# CAN_24bit_airspeed.net
KiCad netlist of a schematic drawn in Altium Designer
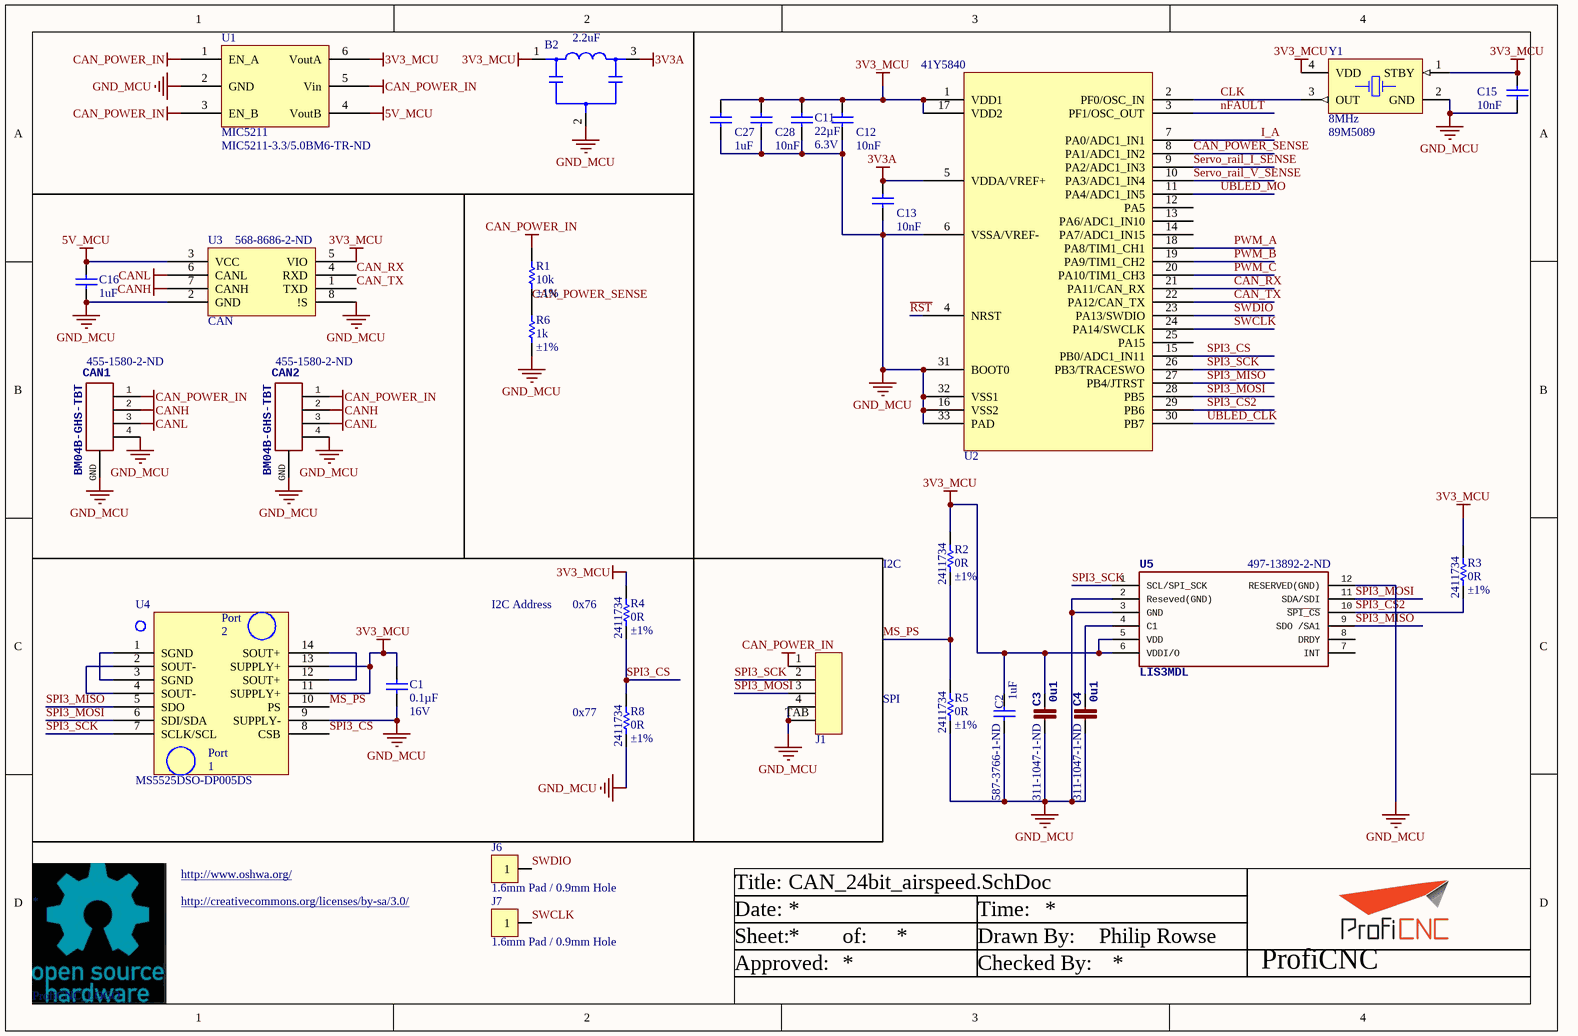
[diagram p0: CAN_24bit_airspeed.SchDoc]

(export (version "E")
  (design (tool "Eeschema 10.0.6"))
  (components
    (comp (ref "*")
      (value "ProfiCNC_LOGO")
      (footprint "ProfiCNC_medium")
      (libsource (lib "ProfiCNC") (part "ProfiCNC_LOGO"))
    )
    (comp (ref "B2")
      (value "2.2uF")
      (footprint "NFM18CC")
      (description "EMIFIL (Capacitor type) Single Circuit Type for Signal Lines")
      (fields
        (field (name "PARTNUMBER") "NFM18PC225B1A3D")
        (field (name "MANUFACTURER") "Murata Electronics North America")
      )
      (libsource (lib "Thiemar Shared Components") (part "NFM18CC222R1C3"))
    )
    (comp (ref "C1")
      (value "0.1µF")
      (footprint "C0402")
      (description "CAP CER 0.1UF 16V X7R 0402")
      (fields
        (field (name "VOLTAGE") "16V")
        (field (name "PART NUMBER") "C01050")
        (field (name "MANUFACTURER") "Murata Electronics North America")
      )
      (libsource (lib "open-components") (part "CAP"))
    )
    (comp (ref "C2")
      (value "1uF")
      (footprint "CAPC1005L")
      (description "CAP CER 1UF 6.3V X5R 0402")
      (fields
        (field (name "PARTNUMBER") "JMK105BJ105KVHF")
        (field (name "SUPPLIER PART NUMBER 1") "587-3766-1-ND")
        (field (name "Comment") "Cap")
      )
      (libsource (lib "Miscellaneous Devices") (part "Cap"))
    )
    (comp (ref "C3")
      (value "0u1")
      (footprint "C0402")
      (description "CAP CER 0.1UF 16V Y5V 0402")
      (fields
        (field (name "SUPPLIER PART NUMBER 1") "311-1047-1-ND")
        (field (name "3DR_PARTNO") "ECM0700")
        (field (name "PARTNO") "CC0402ZRY5V7BB104")
      )
      (libsource (lib "pixhawk2") (part "CAP0402"))
    )
    (comp (ref "C4")
      (value "0u1")
      (footprint "C0402")
      (description "CAP CER 0.1UF 16V Y5V 0402")
      (fields
        (field (name "SUPPLIER PART NUMBER 1") "311-1047-1-ND")
        (field (name "3DR_PARTNO") "ECM0700")
        (field (name "PARTNO") "CC0402ZRY5V7BB104")
      )
      (libsource (lib "pixhawk2") (part "CAP0402"))
    )
    (comp (ref "C11")
      (value "22µF")
      (footprint "C0805")
      (description "CAP CER 22UF 6.3V X5R 0805")
      (fields
        (field (name "VOLTAGE") "6.3V")
        (field (name "PART NUMBER") "C01690")
        (field (name "MANUFACTURER") "Murata Electronics North America")
      )
      (libsource (lib "open-components") (part "CAP"))
    )
    (comp (ref "C12")
      (value "10nF")
      (footprint "CAPC1005L")
      (description "CAP CER 10000PF 50V X7R 0402")
      (fields (field (name "PARTNUMBER") "CGA2B3X7R1H103K050BB"))
      (libsource (lib "Miscellaneous Devices") (part "Cap"))
    )
    (comp (ref "C13")
      (value "10nF")
      (footprint "CAPC1005L")
      (description "CAP CER 10000PF 50V X7R 0402")
      (fields (field (name "PARTNUMBER") "CGA2B3X7R1H103K050BB"))
      (libsource (lib "Miscellaneous Devices") (part "Cap"))
    )
    (comp (ref "C15")
      (value "10nF")
      (footprint "CAPC1005L")
      (description "CAP CER 10000PF 50V X7R 0402")
      (fields (field (name "PARTNUMBER") "CGA2B3X7R1H103K050BB"))
      (libsource (lib "Miscellaneous Devices") (part "Cap"))
    )
    (comp (ref "C16")
      (value "1uF")
      (footprint "CAPC1005L")
      (description "CAP CER 1UF 6.3V X5R 0402")
      (fields (field (name "PARTNUMBER") "JMK105BJ105KVHF") (field (name "Comment") "Cap"))
      (libsource (lib "Miscellaneous Devices") (part "Cap"))
    )
    (comp (ref "C27")
      (value "1uF")
      (footprint "CAPC1005L")
      (description "CAP CER 1UF 6.3V X5R 0402")
      (fields (field (name "PARTNUMBER") "JMK105BJ105KVHF") (field (name "Comment") "Cap"))
      (libsource (lib "Miscellaneous Devices") (part "Cap"))
    )
    (comp (ref "C28")
      (value "10nF")
      (footprint "CAPC1005L")
      (description "CAP CER 10000PF 50V X7R 0402")
      (fields (field (name "PARTNUMBER") "CGA2B3X7R1H103K050BB"))
      (libsource (lib "Miscellaneous Devices") (part "Cap"))
    )
    (comp (ref "CAN1")
      (value "BM04B-GHS-TBT")
      (footprint "BM04-GHS-TBT")
      (fields (field (name "PARTNO") "5023820470") (field (name "SUPPLIER PART NUMBER 1") "455-1580-2-ND"))
      (libsource (lib "ProfiCNC") (part "BM04B-GHS-TBT"))
    )
    (comp (ref "CAN2")
      (value "BM04B-GHS-TBT")
      (footprint "BM04-GHS-TBT")
      (fields (field (name "PARTNO") "5023820470") (field (name "SUPPLIER PART NUMBER 1") "455-1580-2-ND"))
      (libsource (lib "ProfiCNC") (part "BM04B-GHS-TBT"))
    )
    (comp (ref "J1")
      (value "HDR_TAB_1x4")
      (footprint "DF13C-4P-1.25V")
      (description "CONN HEADER 4POS 1.25MM SMD GOLD")
      (fields (field (name "PART NUMBER") "J00015") (field (name "MANUFACTURER") "Hirose Electric Co Ltd"))
      (libsource (lib "open-components") (part "HDR_TAB_1x4"))
    )
    (comp (ref "J6")
      (value "1.6mm Pad / 0.9mm Hole")
      (footprint "1.6mm Pad / 0.9mm Hole")
      (libsource (lib "ProfiCNC") (part "Connector 1x01"))
    )
    (comp (ref "J7")
      (value "1.6mm Pad / 0.9mm Hole")
      (footprint "1.6mm Pad / 0.9mm Hole")
      (libsource (lib "ProfiCNC") (part "Connector 1x01"))
    )
    (comp (ref "R1")
      (value "10k")
      (footprint "R0402")
      (description "RES SMD 10K OHM 1% 1/16W 0402")
      (fields
        (field (name "TOLERANCE") "±1%")
        (field (name "PART NUMBER") "R00142")
        (field (name "MANUFACTURER") "Yageo")
      )
      (libsource (lib "open-components") (part "RES"))
    )
    (comp (ref "R2")
      (value "0R")
      (footprint "R0402")
      (description "RES SMD 0R 1% 1/16W 0402")
      (fields
        (field (name "TOLERANCE") "±1%")
        (field (name "PART NUMBER") "R00094")
        (field (name "MANUFACTURER") "Yageo")
        (field (name "SUPPLIER PART NUMBER 1") "2411734")
      )
      (libsource (lib "open-components") (part "RES"))
    )
    (comp (ref "R3")
      (value "0R")
      (footprint "R0402")
      (description "RES SMD 0R 1% 1/16W 0402")
      (fields
        (field (name "TOLERANCE") "±1%")
        (field (name "PART NUMBER") "R00094")
        (field (name "MANUFACTURER") "Yageo")
        (field (name "SUPPLIER PART NUMBER 1") "2411734")
      )
      (libsource (lib "open-components") (part "RES"))
    )
    (comp (ref "R4")
      (value "0R")
      (footprint "R0402")
      (description "RES SMD 0R 1% 1/16W 0402")
      (fields
        (field (name "TOLERANCE") "±1%")
        (field (name "PART NUMBER") "R00094")
        (field (name "MANUFACTURER") "Yageo")
        (field (name "SUPPLIER PART NUMBER 1") "2411734")
      )
      (libsource (lib "open-components") (part "RES"))
    )
    (comp (ref "R5")
      (value "0R")
      (footprint "R0402")
      (description "RES SMD 0R 1% 1/16W 0402")
      (fields
        (field (name "TOLERANCE") "±1%")
        (field (name "PART NUMBER") "R00094")
        (field (name "MANUFACTURER") "Yageo")
        (field (name "SUPPLIER PART NUMBER 1") "2411734")
      )
      (libsource (lib "open-components") (part "RES"))
    )
    (comp (ref "R6")
      (value "1k")
      (footprint "R0402")
      (description "RES SMD 1K OHM 1% 1/16W 0402")
      (fields
        (field (name "TOLERANCE") "±1%")
        (field (name "PART NUMBER") "R00094")
        (field (name "MANUFACTURER") "Yageo")
      )
      (libsource (lib "open-components") (part "RES"))
    )
    (comp (ref "R8")
      (value "0R")
      (footprint "R0402")
      (description "RES SMD 0R 1% 1/16W 0402")
      (fields
        (field (name "TOLERANCE") "±1%")
        (field (name "PART NUMBER") "R00094")
        (field (name "MANUFACTURER") "Yageo")
        (field (name "SUPPLIER PART NUMBER 1") "2411734")
      )
      (libsource (lib "open-components") (part "RES"))
    )
    (comp (ref "U1")
      (value "MIC5211")
      (footprint "SOT23-6")
      (fields (field (name "SUPPLIER PART NUMBER 1") "MIC5211-3.3/5.0BM6-TR-ND"))
      (libsource (lib "ProfiCNC") (part "MIC5211"))
    )
    (comp (ref "U2")
      (value "IC MCU M4 64KB FLASH 32UFQFPN")
      (footprint "QFN50P500X500X60-32L")
      (description "72 MHz Cortex-M4F MCU with 16 KB RAM, 64 KB flash")
      (fields (field (name "PARTNUMBER") "STM32F302K8U6") (field (name "SUPPLIER PART NUMBER 1") "41Y5840"))
      (libsource (lib "Thiemar Shared Components") (part "STM32F302K8U6"))
    )
    (comp (ref "U3")
      (value "CAN")
      (footprint "SON65P300X100_HS-9N")
      (fields (field (name "SUPPLIER PART NUMBER 1") "568-8686-2-ND"))
      (libsource (lib "ProfiCNC") (part "CAN"))
    )
    (comp (ref "U4")
      (value "MS5525DSO-DP005DS")
      (footprint "MS5525DSO")
      (libsource (lib "ProfiCNC") (part "MS5525DSO-DP"))
    )
    (comp (ref "U5")
      (value "LIS3MDL")
      (footprint "LIS3MDL")
      (fields (field (name "PARTNO") "HMC5983") (field (name "SUPPLIER PART NUMBER 1") "497-13892-2-ND"))
      (libsource (lib "ProfiCNC") (part "LIS3MDL"))
    )
    (comp (ref "Y1")
      (value "8MHz")
      (footprint "CS325")
      (description "3.3V 8MHz XO Oscillator")
      (fields
        (field (name "PARTNUMBER") "ASE-8.000MHZ-LC-T")
        (field (name "MANUFACTURER") "Abracon Corporation")
        (field (name "SUPPLIER PART NUMBER 1") "89M5089")
      )
      (libsource (lib "Thiemar Shared Components") (part "ASE-12.000MHZ"))
    )
  )
  (nets
    (net (code "1") (name "/CAN_POWER_SENSE") (class "Default")
      (node (ref "R1") (pin "2") (pinfunction "2_2") (pintype "passive"))
      (node (ref "R6") (pin "1") (pinfunction "1_1") (pintype "passive"))
      (node (ref "U2") (pin "8") (pinfunction "PA1/ADC1_IN2_8") (pintype "passive"))
    )
    (net (code "2") (name "/CAN_RX") (class "Default")
      (node (ref "U2") (pin "21") (pinfunction "PA11/CAN_RX_21") (pintype "passive"))
      (node (ref "U3") (pin "4") (pinfunction "RXD_4") (pintype "passive"))
    )
    (net (code "3") (name "/CAN_TX") (class "Default")
      (node (ref "U2") (pin "22") (pinfunction "PA12/CAN_TX_22") (pintype "passive"))
      (node (ref "U3") (pin "1") (pinfunction "TXD_1") (pintype "passive"))
    )
    (net (code "4") (name "/CLK") (class "Default")
      (node (ref "U2") (pin "2") (pinfunction "PF0/OSC_IN_2") (pintype "passive"))
      (node (ref "Y1") (pin "3") (pinfunction "OUT_3") (pintype "output"))
    )
    (net (code "5") (name "/I_A") (class "Default")
      (node (ref "U2") (pin "7") (pinfunction "PA0/ADC1_IN1_7") (pintype "passive"))
    )
    (net (code "6") (name "/MS_PS") (class "Default")
      (node (ref "R2") (pin "2") (pinfunction "2_2") (pintype "passive"))
      (node (ref "R5") (pin "1") (pinfunction "1_1") (pintype "passive"))
      (node (ref "U4") (pin "10") (pinfunction "PS_10") (pintype "passive"))
    )
    (net (code "7") (name "/PWM_A") (class "Default")
      (node (ref "U2") (pin "18") (pinfunction "PA8/TIM1_CH1_18") (pintype "passive"))
    )
    (net (code "8") (name "/PWM_B") (class "Default")
      (node (ref "U2") (pin "19") (pinfunction "PA9/TIM1_CH2_19") (pintype "passive"))
    )
    (net (code "9") (name "/PWM_C") (class "Default")
      (node (ref "U2") (pin "20") (pinfunction "PA10/TIM1_CH3_20") (pintype "passive"))
    )
    (net (code "10") (name "/SPI3_CS") (class "Default")
      (node (ref "R4") (pin "2") (pinfunction "2_2") (pintype "passive"))
      (node (ref "R8") (pin "1") (pinfunction "1_1") (pintype "passive"))
      (node (ref "U2") (pin "15") (pinfunction "PB0/ADC1_IN11_15") (pintype "passive"))
      (node (ref "U4") (pin "8") (pinfunction "CSB_8") (pintype "passive"))
    )
    (net (code "11") (name "/SPI3_CS2") (class "Default")
      (node (ref "R3") (pin "2") (pinfunction "2_2") (pintype "passive"))
      (node (ref "U2") (pin "29") (pinfunction "PB6_29") (pintype "passive"))
      (node (ref "U5") (pin "10") (pinfunction "~{SPI_CS}_10") (pintype "passive"))
    )
    (net (code "12") (name "/SPI3_MISO") (class "Default")
      (node (ref "U2") (pin "27") (pinfunction "PB4/JTRST_27") (pintype "passive"))
      (node (ref "U4") (pin "5") (pinfunction "SDO_5") (pintype "passive"))
      (node (ref "U5") (pin "9") (pinfunction "SDO_/SA1_9") (pintype "passive"))
    )
    (net (code "13") (name "/SPI3_MOSI") (class "Default")
      (node (ref "J1") (pin "3") (pinfunction "3_3") (pintype "passive"))
      (node (ref "U2") (pin "28") (pinfunction "PB5_28") (pintype "passive"))
      (node (ref "U4") (pin "6") (pinfunction "SDI/SDA_6") (pintype "passive"))
      (node (ref "U5") (pin "11") (pinfunction "SDA/SDI_11") (pintype "passive"))
    )
    (net (code "14") (name "/SPI3_SCK") (class "Default")
      (node (ref "J1") (pin "2") (pinfunction "2_2") (pintype "passive"))
      (node (ref "U2") (pin "26") (pinfunction "PB3/TRACESWO_26") (pintype "passive"))
      (node (ref "U4") (pin "7") (pinfunction "SCLK/SCL_7") (pintype "passive"))
      (node (ref "U5") (pin "1") (pinfunction "SCL/SPI_SCK_1") (pintype "passive"))
    )
    (net (code "15") (name "/SWCLK") (class "Default")
      (node (ref "J7") (pin "1") (pinfunction "1_1") (pintype "passive"))
      (node (ref "U2") (pin "24") (pinfunction "PA14/SWCLK_24") (pintype "passive"))
    )
    (net (code "16") (name "/SWDIO") (class "Default")
      (node (ref "J6") (pin "1") (pinfunction "1_1") (pintype "passive"))
      (node (ref "U2") (pin "23") (pinfunction "PA13/SWDIO_23") (pintype "passive"))
    )
    (net (code "17") (name "/Servo_rail_I_SENSE") (class "Default")
      (node (ref "U2") (pin "9") (pinfunction "PA2/ADC1_IN3_9") (pintype "passive"))
    )
    (net (code "18") (name "/Servo_rail_V_SENSE") (class "Default")
      (node (ref "U2") (pin "10") (pinfunction "PA3/ADC1_IN4_10") (pintype "passive"))
    )
    (net (code "19") (name "/UBLED_CLK") (class "Default")
      (node (ref "U2") (pin "30") (pinfunction "PB7_30") (pintype "passive"))
    )
    (net (code "20") (name "/UBLED_MO") (class "Default")
      (node (ref "U2") (pin "11") (pinfunction "PA4/ADC1_IN5_11") (pintype "passive"))
    )
    (net (code "21") (name "/nFAULT") (class "Default")
      (node (ref "U2") (pin "3") (pinfunction "PF1/OSC_OUT_3") (pintype "passive"))
    )
    (net (code "22") (name "/~{RST}") (class "Default")
      (node (ref "U2") (pin "4") (pinfunction "NRST_4") (pintype "passive"))
    )
    (net (code "23") (name "3V3A") (class "Default")
      (node (ref "B2") (pin "3") (pinfunction "OUT_3") (pintype "passive"))
      (node (ref "C13") (pin "2") (pinfunction "2_2") (pintype "passive"))
      (node (ref "U2") (pin "5") (pinfunction "VDDA/VREF+_5") (pintype "passive"))
    )
    (net (code "24") (name "3V3_MCU") (class "Default")
      (node (ref "B2") (pin "1") (pinfunction "IN_1") (pintype "passive"))
      (node (ref "C1") (pin "1") (pinfunction "1_1") (pintype "passive"))
      (node (ref "C11") (pin "1") (pinfunction "1_1") (pintype "passive"))
      (node (ref "C12") (pin "2") (pinfunction "2_2") (pintype "passive"))
      (node (ref "C15") (pin "2") (pinfunction "2_2") (pintype "passive"))
      (node (ref "C2") (pin "1") (pinfunction "1_1") (pintype "passive"))
      (node (ref "C27") (pin "1") (pinfunction "1_1") (pintype "passive"))
      (node (ref "C28") (pin "2") (pinfunction "2_2") (pintype "passive"))
      (node (ref "C3") (pin "P$1") (pinfunction "1_P$1") (pintype "passive"))
      (node (ref "R2") (pin "1") (pinfunction "1_1") (pintype "passive"))
      (node (ref "R3") (pin "1") (pinfunction "1_1") (pintype "passive"))
      (node (ref "R4") (pin "1") (pinfunction "1_1") (pintype "passive"))
      (node (ref "U1") (pin "6") (pinfunction "VoutA_6") (pintype "passive"))
      (node (ref "U2") (pin "1") (pinfunction "VDD1_1") (pintype "passive"))
      (node (ref "U2") (pin "17") (pinfunction "VDD2_17") (pintype "passive"))
      (node (ref "U3") (pin "5") (pinfunction "VIO_5") (pintype "passive"))
      (node (ref "U4") (pin "11") (pinfunction "SUPPLY+_11") (pintype "passive"))
      (node (ref "U4") (pin "13") (pinfunction "SUPPLY+_13") (pintype "passive"))
      (node (ref "U5") (pin "5") (pinfunction "VDD_5") (pintype "passive"))
      (node (ref "U5") (pin "6") (pinfunction "VDDI/O_6") (pintype "passive"))
      (node (ref "Y1") (pin "1") (pinfunction "STBY_1") (pintype "input"))
      (node (ref "Y1") (pin "4") (pinfunction "VDD_4") (pintype "power_in"))
    )
    (net (code "25") (name "5V_MCU") (class "Default")
      (node (ref "C16") (pin "2") (pinfunction "2_2") (pintype "passive"))
      (node (ref "U1") (pin "4") (pinfunction "VoutB_4") (pintype "passive"))
      (node (ref "U3") (pin "3") (pinfunction "VCC_3") (pintype "passive"))
    )
    (net (code "26") (name "CANH") (class "Default")
      (node (ref "CAN1") (pin "2") (pinfunction "2_2") (pintype "passive"))
      (node (ref "CAN2") (pin "2") (pinfunction "2_2") (pintype "passive"))
      (node (ref "U3") (pin "7") (pinfunction "CANH_7") (pintype "passive"))
    )
    (net (code "27") (name "CANL") (class "Default")
      (node (ref "CAN1") (pin "3") (pinfunction "3_3") (pintype "passive"))
      (node (ref "CAN2") (pin "3") (pinfunction "3_3") (pintype "passive"))
      (node (ref "U3") (pin "6") (pinfunction "CANL_6") (pintype "passive"))
    )
    (net (code "28") (name "CAN_POWER_IN") (class "Default")
      (node (ref "CAN1") (pin "1") (pinfunction "1_1") (pintype "passive"))
      (node (ref "CAN2") (pin "1") (pinfunction "1_1") (pintype "passive"))
      (node (ref "J1") (pin "1") (pinfunction "1_1") (pintype "passive"))
      (node (ref "R1") (pin "1") (pinfunction "1_1") (pintype "passive"))
      (node (ref "U1") (pin "1") (pinfunction "EN_A_1") (pintype "power_in"))
      (node (ref "U1") (pin "3") (pinfunction "EN_B_3") (pintype "passive"))
      (node (ref "U1") (pin "5") (pinfunction "Vin_5") (pintype "passive"))
    )
    (net (code "29") (name "GND_MCU") (class "Default")
      (node (ref "B2") (pin "2") (pinfunction "GND_2") (pintype "passive"))
      (node (ref "C1") (pin "2") (pinfunction "2_2") (pintype "passive"))
      (node (ref "C11") (pin "2") (pinfunction "2_2") (pintype "passive"))
      (node (ref "C12") (pin "1") (pinfunction "1_1") (pintype "passive"))
      (node (ref "C13") (pin "1") (pinfunction "1_1") (pintype "passive"))
      (node (ref "C15") (pin "1") (pinfunction "1_1") (pintype "passive"))
      (node (ref "C16") (pin "1") (pinfunction "1_1") (pintype "passive"))
      (node (ref "C2") (pin "2") (pinfunction "2_2") (pintype "passive"))
      (node (ref "C27") (pin "2") (pinfunction "2_2") (pintype "passive"))
      (node (ref "C28") (pin "1") (pinfunction "1_1") (pintype "passive"))
      (node (ref "C3") (pin "P$2") (pinfunction "2_P$2") (pintype "passive"))
      (node (ref "C4") (pin "P$2") (pinfunction "2_P$2") (pintype "passive"))
      (node (ref "CAN1") (pin "4") (pinfunction "4_4") (pintype "passive"))
      (node (ref "CAN1") (pin "GND") (pinfunction "GND_GND") (pintype "passive"))
      (node (ref "CAN2") (pin "4") (pinfunction "4_4") (pintype "passive"))
      (node (ref "CAN2") (pin "GND") (pinfunction "GND_GND") (pintype "passive"))
      (node (ref "J1") (pin "4") (pinfunction "4_4") (pintype "passive"))
      (node (ref "J1") (pin "TAB") (pinfunction "TAB_TAB") (pintype "passive"))
      (node (ref "R5") (pin "2") (pinfunction "2_2") (pintype "passive"))
      (node (ref "R6") (pin "2") (pinfunction "2_2") (pintype "passive"))
      (node (ref "R8") (pin "2") (pinfunction "2_2") (pintype "passive"))
      (node (ref "U1") (pin "2") (pinfunction "GND_2") (pintype "power_in"))
      (node (ref "U2") (pin "16") (pinfunction "VSS2_16") (pintype "passive"))
      (node (ref "U2") (pin "31") (pinfunction "BOOT0_31") (pintype "passive"))
      (node (ref "U2") (pin "32") (pinfunction "VSS1_32") (pintype "passive"))
      (node (ref "U2") (pin "33") (pinfunction "PAD_33") (pintype "passive"))
      (node (ref "U2") (pin "6") (pinfunction "VSSA/VREF-_6") (pintype "passive"))
      (node (ref "U3") (pin "2") (pinfunction "GND_2") (pintype "passive"))
      (node (ref "U3") (pin "8") (pinfunction "!S_8") (pintype "passive"))
      (node (ref "U4") (pin "9") (pinfunction "SUPPLY-_9") (pintype "passive"))
      (node (ref "U5") (pin "12") (pinfunction "RESERVED(GND)_12") (pintype "passive"))
      (node (ref "U5") (pin "2") (pinfunction "Reseved(GND)_2") (pintype "power_in"))
      (node (ref "U5") (pin "3") (pinfunction "GND_3") (pintype "passive"))
      (node (ref "Y1") (pin "2") (pinfunction "GND_2") (pintype "power_in"))
    )
    (net (code "30") (name "Net-(C4-1)") (class "Default")
      (node (ref "C4") (pin "P$1") (pinfunction "1_P$1") (pintype "passive"))
      (node (ref "U5") (pin "4") (pinfunction "C1_4") (pintype "passive"))
    )
    (net (code "31") (name "Net-(U4-SGND-Pad1)") (class "Default")
      (node (ref "U4") (pin "1") (pinfunction "SGND_1") (pintype "passive"))
      (node (ref "U4") (pin "3") (pinfunction "SGND_3") (pintype "passive"))
    )
    (net (code "32") (name "Net-(U4-SOUT+-Pad12)") (class "Default")
      (node (ref "U4") (pin "12") (pinfunction "SOUT+_12") (pintype "passive"))
      (node (ref "U4") (pin "14") (pinfunction "SOUT+_14") (pintype "passive"))
    )
    (net (code "33") (name "Net-(U4-SOUT--Pad2)") (class "Default")
      (node (ref "U4") (pin "2") (pinfunction "SOUT-_2") (pintype "passive"))
      (node (ref "U4") (pin "4") (pinfunction "SOUT-_4") (pintype "passive"))
    )
    (net (code "34") (name "unconnected-(U2-PA5-Pad12)") (class "Default")
      (node (ref "U2") (pin "12") (pinfunction "PA5_12") (pintype "passive"))
    )
    (net (code "35") (name "unconnected-(U2-PA6{slash}ADC1_IN10-Pad13)") (class "Default")
      (node (ref "U2") (pin "13") (pinfunction "PA6/ADC1_IN10_13") (pintype "passive"))
    )
    (net (code "36") (name "unconnected-(U2-PA7{slash}ADC1_IN15-Pad14)") (class "Default")
      (node (ref "U2") (pin "14") (pinfunction "PA7/ADC1_IN15_14") (pintype "passive"))
    )
    (net (code "37") (name "unconnected-(U2-PA15-Pad25)") (class "Default")
      (node (ref "U2") (pin "25") (pinfunction "PA15_25") (pintype "passive"))
    )
    (net (code "38") (name "unconnected-(U5-DRDY-Pad8)") (class "Default")
      (node (ref "U5") (pin "8") (pinfunction "DRDY_8") (pintype "passive"))
    )
    (net (code "39") (name "unconnected-(U5-INT-Pad7)") (class "Default")
      (node (ref "U5") (pin "7") (pinfunction "INT_7") (pintype "passive"))
    )
  )
)
